# Drive.net
KiCad netlist of a schematic drawn in Altium Designer
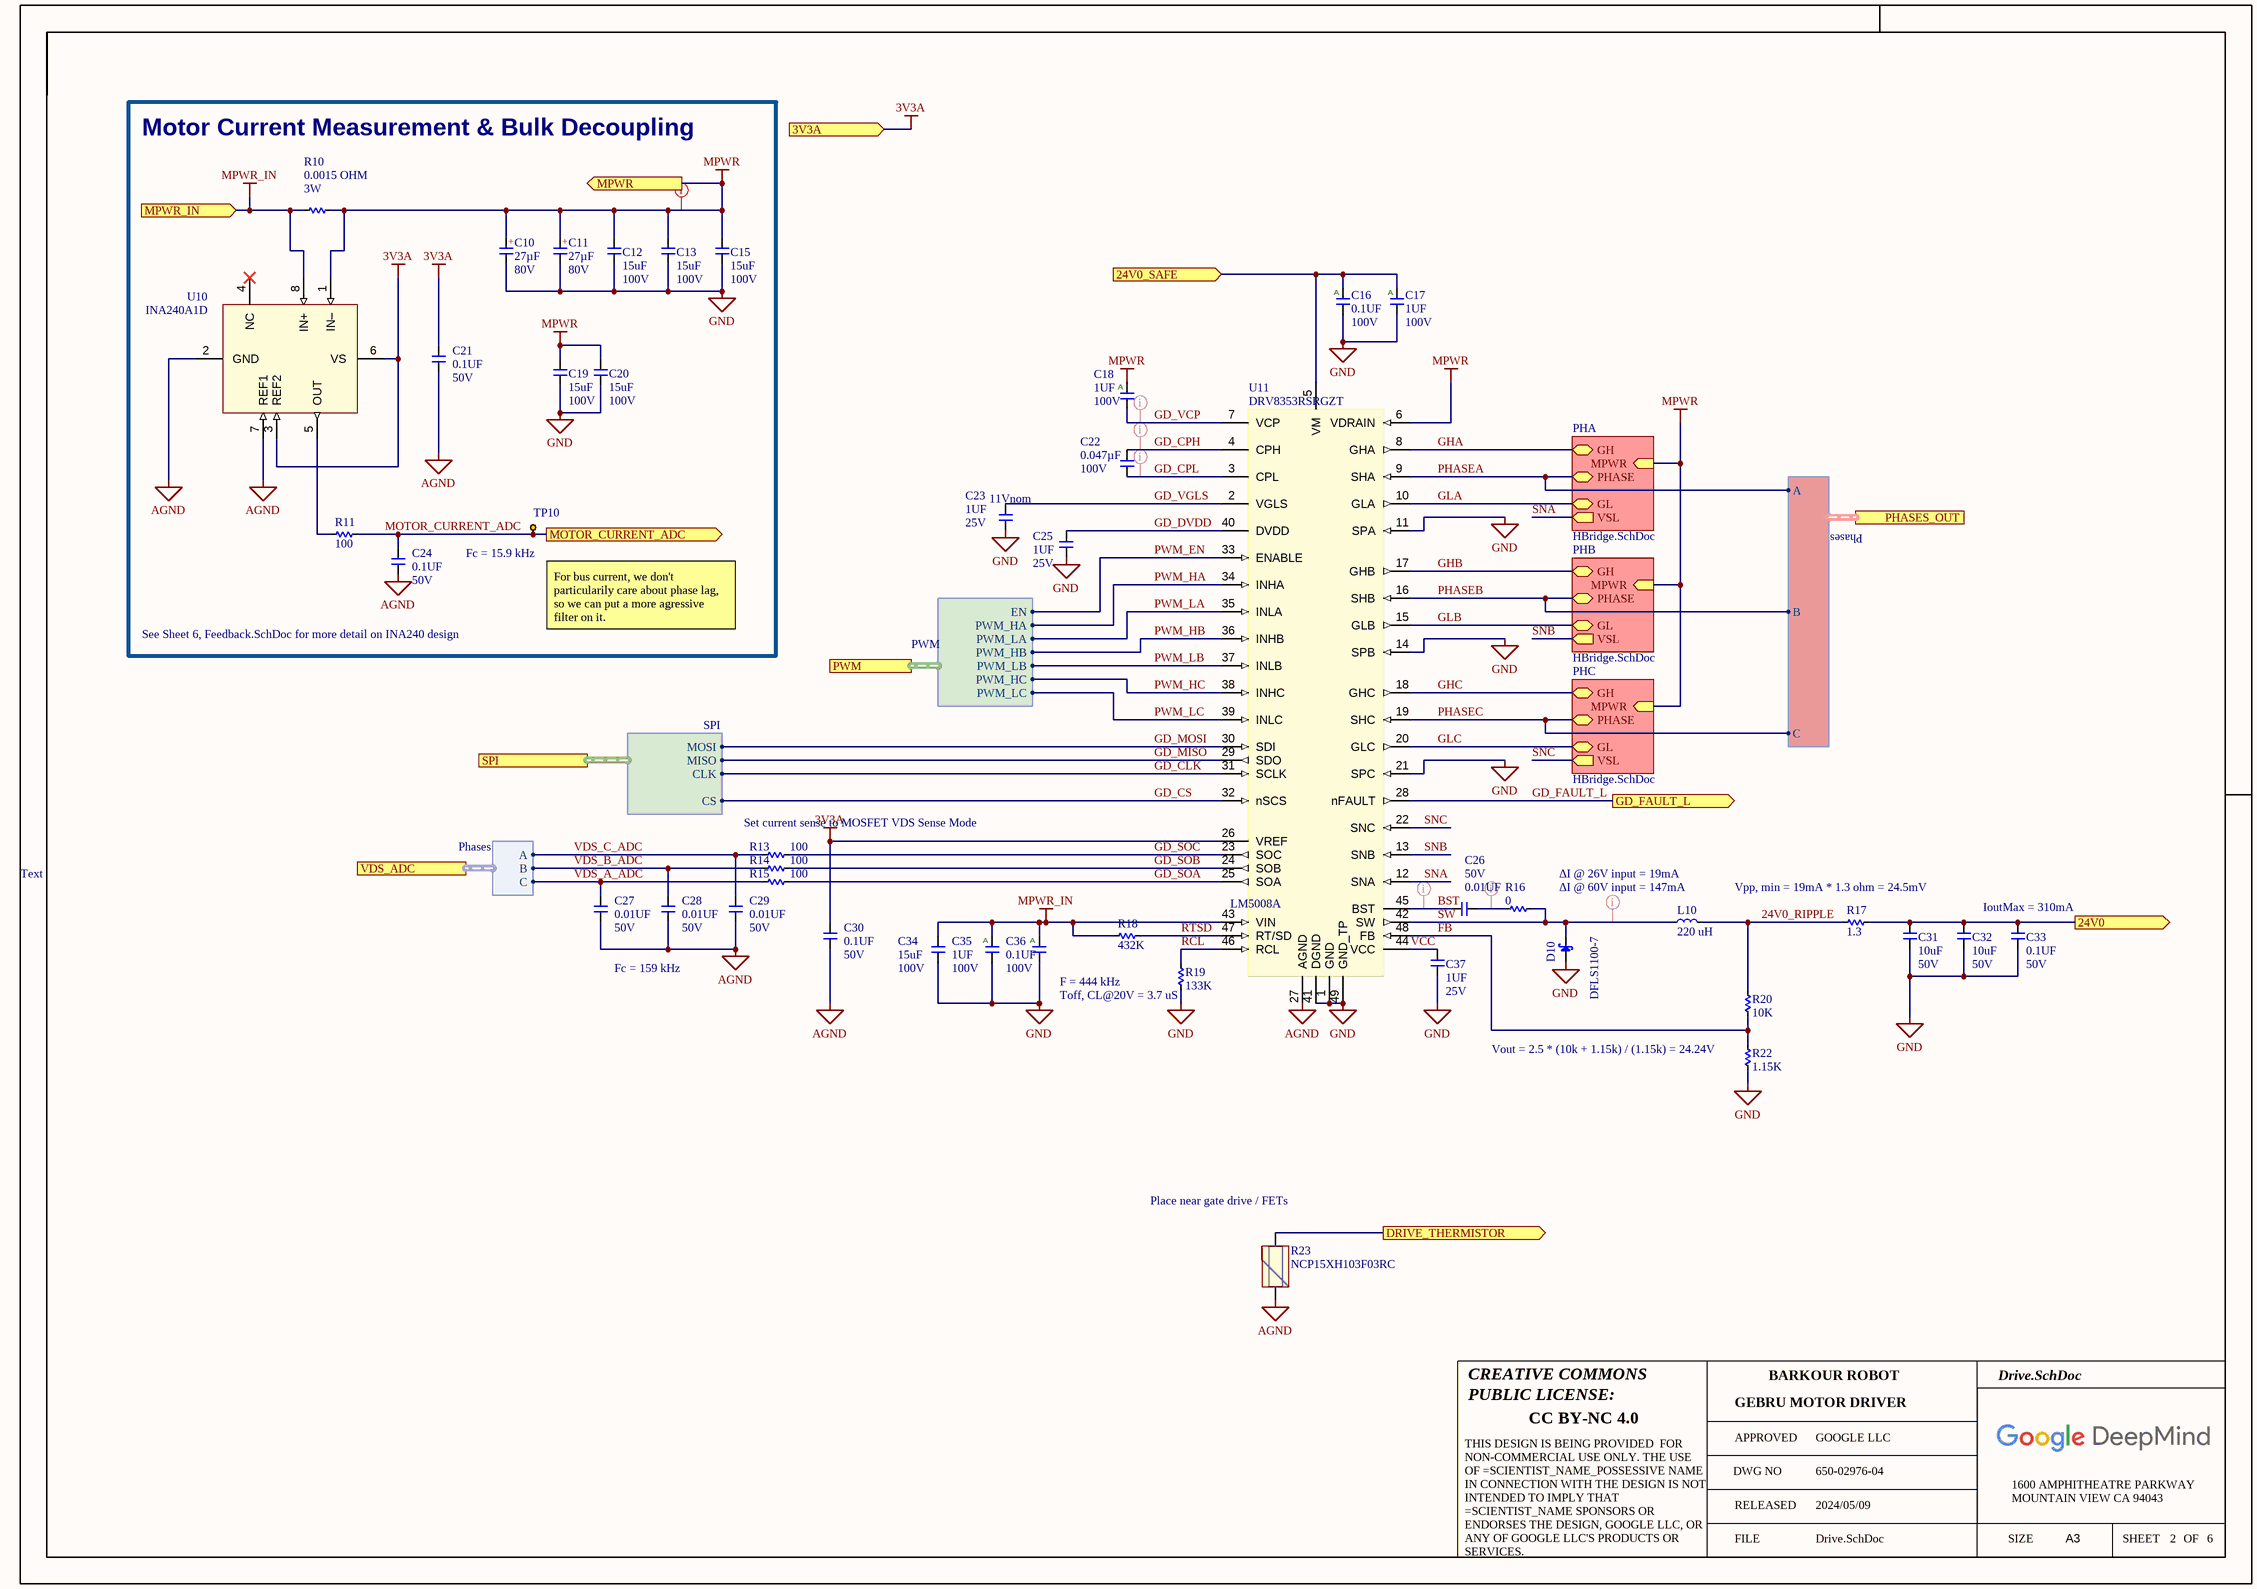
[diagram p0: Drive.SchDoc]

(export (version "E")
  (design (tool "Eeschema 10.0.6"))
  (components
    (comp (ref "C10")
      (value "27µF")
      (footprint "WURTH_WCAP-PTHR_10x12.5x5")
      (description "WCAP-PTHR ALUMINUM POLYMER CAP")
      (fields
        (field (name "MANUFACTURER") "Wurth Electronics")
        (field (name "MANUFACTURER PART NUMBER") "870056175004")
        (field (name "VOLTAGE RATING") "80V")
      )
      (libsource (lib "Components") (part "CAP-POL"))
    )
    (comp (ref "C11")
      (value "27µF")
      (footprint "WURTH_WCAP-PTHR_10x12.5x5")
      (description "WCAP-PTHR ALUMINUM POLYMER CAP")
      (fields
        (field (name "MANUFACTURER") "Wurth Electronics")
        (field (name "MANUFACTURER PART NUMBER") "870056175004")
        (field (name "VOLTAGE RATING") "80V")
      )
      (libsource (lib "Components") (part "CAP-POL"))
    )
    (comp (ref "C12")
      (value "15uF")
      (footprint "C2220")
      (description "CAP, CER, X7S, 15uF, 100V, 20%, 2220, 2.8mm T")
      (fields (field (name "MFG") "TDK") (field (name "VOLTAGE") "100V") (field (name "TOLERANCE") "20%"))
      (libsource (lib "AltiumReleaseLibDB") (part "__Template_Cap"))
    )
    (comp (ref "C13")
      (value "15uF")
      (footprint "C2220")
      (description "CAP, CER, X7S, 15uF, 100V, 20%, 2220, 2.8mm T")
      (fields (field (name "MFG") "TDK") (field (name "VOLTAGE") "100V") (field (name "TOLERANCE") "20%"))
      (libsource (lib "AltiumReleaseLibDB") (part "__Template_Cap"))
    )
    (comp (ref "C15")
      (value "15uF")
      (footprint "C2220")
      (description "CAP, CER, X7S, 15uF, 100V, 20%, 2220, 2.8mm T")
      (fields (field (name "MFG") "TDK") (field (name "VOLTAGE") "100V") (field (name "TOLERANCE") "20%"))
      (libsource (lib "AltiumReleaseLibDB") (part "__Template_Cap"))
    )
    (comp (ref "C16")
      (value "0.1UF")
      (footprint "C0603")
      (description "CAP, CER, X7S, 0.1uF, 100V, 10%, 0603, AUTOGRADE")
      (fields (field (name "MFG") "TDK") (field (name "VOLTAGE") "100V") (field (name "TOLERANCE") "10%"))
      (libsource (lib "AltiumReleaseLibDB") (part "__Template_Cap_Auto"))
    )
    (comp (ref "C17")
      (value "1UF")
      (footprint "C0805")
      (description "CAP, CER, X7S, 1uF, 20%, 100V, 0805")
      (fields (field (name "MFG") "TDK") (field (name "VOLTAGE") "100V") (field (name "TOLERANCE") "20%"))
      (libsource (lib "AltiumReleaseLibDB") (part "__Template_Cap_Auto"))
    )
    (comp (ref "C18")
      (value "1UF")
      (footprint "C0805")
      (description "CAP, CER, X7S, 1uF, 20%, 100V, 0805")
      (fields (field (name "MFG") "TDK") (field (name "VOLTAGE") "100V") (field (name "TOLERANCE") "20%"))
      (libsource (lib "AltiumReleaseLibDB") (part "__Template_Cap_Auto"))
    )
    (comp (ref "C19")
      (value "15uF")
      (footprint "C2220")
      (description "CAP, CER, X7S, 15uF, 100V, 20%, 2220, 2.8mm T")
      (fields (field (name "MFG") "TDK") (field (name "VOLTAGE") "100V") (field (name "TOLERANCE") "20%"))
      (libsource (lib "AltiumReleaseLibDB") (part "__Template_Cap"))
    )
    (comp (ref "C20")
      (value "15uF")
      (footprint "C2220")
      (description "CAP, CER, X7S, 15uF, 100V, 20%, 2220, 2.8mm T")
      (fields (field (name "MFG") "TDK") (field (name "VOLTAGE") "100V") (field (name "TOLERANCE") "20%"))
      (libsource (lib "AltiumReleaseLibDB") (part "__Template_Cap"))
    )
    (comp (ref "C21")
      (value "0.1UF")
      (footprint "C0402")
      (description "CAP, CER, X5R, 0.1uF, 10%, 50V, 0402, 0.55mm")
      (fields (field (name "MFG") "YAGEO") (field (name "VOLTAGE") "50V") (field (name "TOLERANCE") "10%"))
      (libsource (lib "AltiumReleaseLibDB") (part "__Template_Cap"))
    )
    (comp (ref "C22")
      (value "0.047µF")
      (footprint "C0603Y")
      (description "CAP, CER, X7R, 0.047uF, 100V, 10%, 0603, AUTOGRADE")
      (fields
        (field (name "MFG") "Samsung Electro-Mechanics")
        (field (name "VOLTAGE") "100V")
        (field (name "TOLERANCE") "10%")
      )
      (libsource (lib "AltiumReleaseLibDB") (part "__Template_Cap"))
    )
    (comp (ref "C23")
      (value "1UF")
      (footprint "C0402")
      (description "CAP, CER, X5R, 1uF, 10%, 25V, 0402")
      (fields (field (name "MFG") "TDK") (field (name "VOLTAGE") "25V") (field (name "TOLERANCE") "10%"))
      (libsource (lib "AltiumReleaseLibDB") (part "__Template_Cap"))
    )
    (comp (ref "C24")
      (value "0.1UF")
      (footprint "C0402")
      (description "CAP, CER, X5R, 0.1uF, 10%, 50V, 0402, 0.55mm")
      (fields (field (name "MFG") "YAGEO") (field (name "VOLTAGE") "50V") (field (name "TOLERANCE") "10%"))
      (libsource (lib "AltiumReleaseLibDB") (part "__Template_Cap"))
    )
    (comp (ref "C25")
      (value "1UF")
      (footprint "C0402")
      (description "CAP, CER, X5R, 1uF, 10%, 25V, 0402")
      (fields (field (name "MFG") "TDK") (field (name "VOLTAGE") "25V") (field (name "TOLERANCE") "10%"))
      (libsource (lib "AltiumReleaseLibDB") (part "__Template_Cap"))
    )
    (comp (ref "C26")
      (value "0.01UF")
      (footprint "C0402")
      (description "CAP, CER, X7R, 0.01uF, 50V, 20%, 0402, 0.56mm T")
      (fields (field (name "MFG") "KEMET") (field (name "VOLTAGE") "50V") (field (name "TOLERANCE") "20%"))
      (libsource (lib "AltiumReleaseLibDB") (part "__Template_Cap"))
    )
    (comp (ref "C27")
      (value "0.01UF")
      (footprint "C0402")
      (description "CAP, CER, X7R, 0.01uF, 50V, 20%, 0402, 0.56mm T")
      (fields (field (name "MFG") "KEMET") (field (name "VOLTAGE") "50V") (field (name "TOLERANCE") "20%"))
      (libsource (lib "AltiumReleaseLibDB") (part "__Template_Cap"))
    )
    (comp (ref "C28")
      (value "0.01UF")
      (footprint "C0402")
      (description "CAP, CER, X7R, 0.01uF, 50V, 20%, 0402, 0.56mm T")
      (fields (field (name "MFG") "KEMET") (field (name "VOLTAGE") "50V") (field (name "TOLERANCE") "20%"))
      (libsource (lib "AltiumReleaseLibDB") (part "__Template_Cap"))
    )
    (comp (ref "C29")
      (value "0.01UF")
      (footprint "C0402")
      (description "CAP, CER, X7R, 0.01uF, 50V, 20%, 0402, 0.56mm T")
      (fields (field (name "MFG") "KEMET") (field (name "VOLTAGE") "50V") (field (name "TOLERANCE") "20%"))
      (libsource (lib "AltiumReleaseLibDB") (part "__Template_Cap"))
    )
    (comp (ref "C30")
      (value "0.1UF")
      (footprint "C0402")
      (description "CAP, CER, X5R, 0.1uF, 10%, 50V, 0402, 0.55mm")
      (fields (field (name "MFG") "YAGEO") (field (name "VOLTAGE") "50V") (field (name "TOLERANCE") "10%"))
      (libsource (lib "AltiumReleaseLibDB") (part "__Template_Cap"))
    )
    (comp (ref "C31")
      (value "10uF")
      (footprint "C1210_H2.7mm")
      (description "CAP, CER, X5R, 10uF, 50V, 20%, 1210")
      (fields
        (field (name "MFG") "TAIYO YUDEN")
        (field (name "VOLTAGE") "50V")
        (field (name "TOLERANCE") "20%")
      )
      (libsource (lib "AltiumReleaseLibDB") (part "__Template_Cap"))
    )
    (comp (ref "C32")
      (value "10uF")
      (footprint "C1210_H2.7mm")
      (description "CAP, CER, X5R, 10uF, 50V, 20%, 1210")
      (fields
        (field (name "MFG") "TAIYO YUDEN")
        (field (name "VOLTAGE") "50V")
        (field (name "TOLERANCE") "20%")
      )
      (libsource (lib "AltiumReleaseLibDB") (part "__Template_Cap"))
    )
    (comp (ref "C33")
      (value "0.1UF")
      (footprint "C0402")
      (description "CAP, CER, X5R, 0.1uF, 10%, 50V, 0402, 0.55mm")
      (fields (field (name "MFG") "YAGEO") (field (name "VOLTAGE") "50V") (field (name "TOLERANCE") "10%"))
      (libsource (lib "AltiumReleaseLibDB") (part "__Template_Cap"))
    )
    (comp (ref "C34")
      (value "15uF")
      (footprint "C2220")
      (description "CAP, CER, X7S, 15uF, 100V, 20%, 2220, 2.8mm T")
      (fields (field (name "MFG") "TDK") (field (name "VOLTAGE") "100V") (field (name "TOLERANCE") "20%"))
      (libsource (lib "AltiumReleaseLibDB") (part "__Template_Cap"))
    )
    (comp (ref "C35")
      (value "1UF")
      (footprint "C0805")
      (description "CAP, CER, X7S, 1uF, 20%, 100V, 0805")
      (fields (field (name "MFG") "TDK") (field (name "VOLTAGE") "100V") (field (name "TOLERANCE") "20%"))
      (libsource (lib "AltiumReleaseLibDB") (part "__Template_Cap_Auto"))
    )
    (comp (ref "C36")
      (value "0.1UF")
      (footprint "C0603")
      (description "CAP, CER, X7S, 0.1uF, 100V, 10%, 0603, AUTOGRADE")
      (fields (field (name "MFG") "TDK") (field (name "VOLTAGE") "100V") (field (name "TOLERANCE") "10%"))
      (libsource (lib "AltiumReleaseLibDB") (part "__Template_Cap_Auto"))
    )
    (comp (ref "C37")
      (value "1UF")
      (footprint "C0402")
      (description "CAP, CER, X5R, 1uF, 10%, 25V, 0402")
      (fields (field (name "MFG") "TDK") (field (name "VOLTAGE") "25V") (field (name "TOLERANCE") "10%"))
      (libsource (lib "AltiumReleaseLibDB") (part "__Template_Cap"))
    )
    (comp (ref "D10")
      (value "DFLS1100-7")
      (footprint "POWERDI123_DFLS1100-7")
      (description "DIODE, SCHOTTKY, 100V, 1A, POWERDI123")
      (fields
        (field (name "MFG") "Diodes Incorporated")
        (field (name "Comment") "__Template_Diode_Schottky_A/K")
      )
      (libsource (lib "AltiumReleaseLibDB") (part "__Template_Diode_Schottky_A/K"))
    )
    (comp (ref "L10")
      (value "220 uH")
      (footprint "IND_MSS7348")
      (description "IND, WIREWOUND, SHIELDED, 220uH, 0.74A, 20%, DCR 0.624, SMD, AUTOGRADE")
      (fields (field (name "MFG") "Coilcraft") (field (name "TOLERANCE") "20%"))
      (libsource (lib "AltiumReleaseLibDB") (part "__Template_Inductor"))
    )
    (comp (ref "R10")
      (value "0.0015 OHM")
      (footprint "R2512_H0.8MM")
      (description "RES, 0.0015, 1%, 3W, 2512")
      (fields
        (field (name "MFG") "TE Connectivity Passive Product")
        (field (name "POWER") "3W")
        (field (name "TOLERANCE") "1%")
      )
      (libsource (lib "AltiumReleaseLibDB") (part "__Template_Resistor"))
    )
    (comp (ref "R11")
      (value "100")
      (footprint "R0402")
      (description "RES, 100, 1%, 1/10W, 0402, AUTO GRADE")
      (fields (field (name "MFG") "PANASONIC") (field (name "POWER") "1/10W"))
      (libsource (lib "AltiumReleaseLibDB") (part "__Template_Resistor"))
    )
    (comp (ref "R13")
      (value "100")
      (footprint "R0402")
      (description "RES, 100, 1%, 1/10W, 0402, AUTO GRADE")
      (fields (field (name "MFG") "PANASONIC") (field (name "POWER") "1/10W"))
      (libsource (lib "AltiumReleaseLibDB") (part "__Template_Resistor"))
    )
    (comp (ref "R14")
      (value "100")
      (footprint "R0402")
      (description "RES, 100, 1%, 1/10W, 0402, AUTO GRADE")
      (fields (field (name "MFG") "PANASONIC") (field (name "POWER") "1/10W"))
      (libsource (lib "AltiumReleaseLibDB") (part "__Template_Resistor"))
    )
    (comp (ref "R15")
      (value "100")
      (footprint "R0402")
      (description "RES, 100, 1%, 1/10W, 0402, AUTO GRADE")
      (fields (field (name "MFG") "PANASONIC") (field (name "POWER") "1/10W"))
      (libsource (lib "AltiumReleaseLibDB") (part "__Template_Resistor"))
    )
    (comp (ref "R16")
      (value "0")
      (footprint "R0402")
      (description "RES, 0, JUMPER, 1/16W, 0402")
      (fields (field (name "MFG") "YAGEO") (field (name "POWER") "1/16W"))
      (libsource (lib "AltiumReleaseLibDB") (part "__Template_Resistor"))
    )
    (comp (ref "R17")
      (value "1.3")
      (footprint "R0805")
      (description "RES, 1.3, 1%, 1/2W, AUTOGRADE, 0805")
      (fields (field (name "MFG") "Panasonic Electronic Components") (field (name "POWER") "1/2W"))
      (libsource (lib "AltiumReleaseLibDB") (part "__Template_Resistor"))
    )
    (comp (ref "R18")
      (value "432K")
      (footprint "R0402")
      (description "RES, 432K, 1%, 1/16W, 0402")
      (fields (field (name "MFG") "VISHAY") (field (name "POWER") "1/16W"))
      (libsource (lib "AltiumReleaseLibDB") (part "__Template_Resistor"))
    )
    (comp (ref "R19")
      (value "133K")
      (footprint "R0402")
      (description "RES, 133K, 1%, 1/16W, 0402, AUTOGRADE")
      (fields (field (name "MFG") "VISHAY") (field (name "POWER") "1/16W"))
      (libsource (lib "AltiumReleaseLibDB") (part "__Template_Resistor"))
    )
    (comp (ref "R20")
      (value "10K")
      (footprint "R0402")
      (description "RES, 10K, 1%, 1/10W, 0402, AUTOGRADE")
      (fields (field (name "MFG") "PANASONIC") (field (name "POWER") "1/10W"))
      (libsource (lib "AltiumReleaseLibDB") (part "__Template_Resistor"))
    )
    (comp (ref "R22")
      (value "1.15K")
      (footprint "R0402")
      (description "RES, 1.15K, 1%, 1/16W, 0402")
      (fields (field (name "MFG") "VISHAY") (field (name "POWER") "1/16W"))
      (libsource (lib "AltiumReleaseLibDB") (part "__Template_Resistor"))
    )
    (comp (ref "R23")
      (value "__Template_Thermistor")
      (footprint "R0402_H0.55MM")
      (description "SENSOR, THERMISTOR, NTC, 10K, 1%, 3380K, 100mW, 0402")
      (fields (field (name "MFG") "Murata Electronics") (field (name "MFG P/N") "NCP15XH103F03RC"))
      (libsource (lib "AltiumReleaseLibDB") (part "__Template_Thermistor"))
    )
    (comp (ref "TP10")
      (value "TEST_KEYSTONE5015")
      (footprint "TP_KEYSTONE_5015")
      (description "PC TEST POINT MINIATURE SMT")
      (fields
        (field (name "MANUFACTURER") "Keystone Electronics")
        (field (name "MANUFACTURER PART NUMBER") "5015")
      )
      (libsource (lib "miscellaneous") (part "TEST_KEYSTONE5015"))
    )
    (comp (ref "U10")
      (value "INA240A1D")
      (footprint "TI SOIC-8 D0008A")
      (fields (field (name "MANUFACTURER") "Texas Instruments"))
      (libsource (lib "MiscSch1") (part "INA240A1"))
    )
    (comp (ref "U11")
      (value "MOTOR_DRIVE_DRV8353RSRGZT")
      (footprint "VQFN50P700X700X100-48-TP_TP-CUST_NO_VIAS")
      (description "IC, MOTOR DRIVER, DRV8353, MULTIPHASE, BLDC, HALF BRIDGE, POWER MOSFET, 6V TO 95V VIN, VQFN-48")
      (fields (field (name "MFG") "Texas Instruments") (field (name "MFG P/N") "DRV8353RSRGZT"))
      (libsource (lib "AltiumReleaseLibDB") (part "MOTOR_DRIVE_DRV8353RSRGZT"))
    )
  )
  (nets
    (net (code "4") (name "/24V0") (class "Default")
      (node (ref "C31") (pin "1") (pintype "passive"))
      (node (ref "C32") (pin "1") (pintype "passive"))
      (node (ref "C33") (pin "1") (pintype "passive"))
      (node (ref "R17") (pin "2") (pintype "passive"))
    )
    (net (code "5") (name "/24V0_RIPPLE") (class "Default")
      (node (ref "L10") (pin "2") (pintype "passive"))
      (node (ref "R17") (pin "1") (pintype "passive"))
      (node (ref "R20") (pin "2") (pintype "passive"))
    )
    (net (code "6") (name "/24V0_SAFE") (class "Default")
      (node (ref "C16") (pin "1") (pintype "passive"))
      (node (ref "C17") (pin "1") (pintype "passive"))
      (node (ref "U11") (pin "5") (pinfunction "VM_5") (pintype "power_in"))
    )
    (net (code "7") (name "/BST") (class "Default")
      (node (ref "C26") (pin "1") (pintype "passive"))
      (node (ref "U11") (pin "45") (pinfunction "BST_45") (pintype "power_in"))
    )
    (net (code "8") (name "/DRIVE_THERMISTOR") (class "Default")
      (node (ref "R23") (pin "1") (pintype "passive"))
    )
    (net (code "9") (name "/FB") (class "Default")
      (node (ref "R20") (pin "1") (pintype "passive"))
      (node (ref "R22") (pin "2") (pintype "passive"))
      (node (ref "U11") (pin "48") (pinfunction "FB_48") (pintype "input"))
    )
    (net (code "10") (name "/GD_CLK") (class "Default")
      (node (ref "U11") (pin "31") (pinfunction "SCLK_31") (pintype "input"))
    )
    (net (code "11") (name "/GD_CPH") (class "Default")
      (node (ref "C22") (pin "1") (pintype "passive"))
      (node (ref "U11") (pin "4") (pinfunction "CPH_4") (pintype "power_in"))
    )
    (net (code "12") (name "/GD_CPL") (class "Default")
      (node (ref "C22") (pin "2") (pintype "passive"))
      (node (ref "U11") (pin "3") (pinfunction "CPL_3") (pintype "power_in"))
    )
    (net (code "13") (name "/GD_CS") (class "Default")
      (node (ref "U11") (pin "32") (pinfunction "nSCS_32") (pintype "input"))
    )
    (net (code "14") (name "/GD_DVDD") (class "Default")
      (node (ref "C25") (pin "1") (pintype "passive"))
      (node (ref "U11") (pin "40") (pinfunction "DVDD_40") (pintype "power_in"))
    )
    (net (code "15") (name "/GD_FAULT_L") (class "Default")
      (node (ref "U11") (pin "28") (pinfunction "nFAULT_28") (pintype "output"))
    )
    (net (code "16") (name "/GD_MISO") (class "Default")
      (node (ref "U11") (pin "29") (pinfunction "SDO_29") (pintype "output"))
    )
    (net (code "17") (name "/GD_MOSI") (class "Default")
      (node (ref "U11") (pin "30") (pinfunction "SDI_30") (pintype "input"))
    )
    (net (code "18") (name "/GD_SOA") (class "Default")
      (node (ref "R15") (pin "2") (pintype "passive"))
      (node (ref "U11") (pin "25") (pinfunction "SOA_25") (pintype "output"))
    )
    (net (code "19") (name "/GD_SOB") (class "Default")
      (node (ref "R14") (pin "2") (pintype "passive"))
      (node (ref "U11") (pin "24") (pinfunction "SOB_24") (pintype "output"))
    )
    (net (code "20") (name "/GD_SOC") (class "Default")
      (node (ref "R13") (pin "2") (pintype "passive"))
      (node (ref "U11") (pin "23") (pinfunction "SOC_23") (pintype "output"))
    )
    (net (code "21") (name "/GD_VCP") (class "Default")
      (node (ref "C18") (pin "2") (pintype "passive"))
      (node (ref "U11") (pin "7") (pinfunction "VCP_7") (pintype "power_in"))
    )
    (net (code "22") (name "/GD_VGLS") (class "Default")
      (node (ref "C23") (pin "1") (pintype "passive"))
      (node (ref "U11") (pin "2") (pinfunction "VGLS_2") (pintype "power_in"))
    )
    (net (code "23") (name "/GHA") (class "Default")
      (node (ref "U11") (pin "8") (pinfunction "GHA_8") (pintype "output"))
    )
    (net (code "24") (name "/GHB") (class "Default")
      (node (ref "U11") (pin "17") (pinfunction "GHB_17") (pintype "output"))
    )
    (net (code "25") (name "/GHC") (class "Default")
      (node (ref "U11") (pin "18") (pinfunction "GHC_18") (pintype "output"))
    )
    (net (code "26") (name "/GLA") (class "Default")
      (node (ref "U11") (pin "10") (pinfunction "GLA_10") (pintype "output"))
    )
    (net (code "27") (name "/GLB") (class "Default")
      (node (ref "U11") (pin "15") (pinfunction "GLB_15") (pintype "output"))
    )
    (net (code "28") (name "/GLC") (class "Default")
      (node (ref "U11") (pin "20") (pinfunction "GLC_20") (pintype "output"))
    )
    (net (code "29") (name "/MOTOR_CURRENT_ADC") (class "Default")
      (node (ref "C24") (pin "1") (pintype "passive"))
      (node (ref "R11") (pin "2") (pintype "passive"))
      (node (ref "TP10") (pin "1") (pintype "passive"))
    )
    (net (code "30") (name "/PHASEA") (class "Default")
      (node (ref "U11") (pin "9") (pinfunction "SHA_9") (pintype "input"))
    )
    (net (code "31") (name "/PHASEB") (class "Default")
      (node (ref "U11") (pin "16") (pinfunction "SHB_16") (pintype "input"))
    )
    (net (code "32") (name "/PHASEC") (class "Default")
      (node (ref "U11") (pin "19") (pinfunction "SHC_19") (pintype "input"))
    )
    (net (code "33") (name "/PWM_EN") (class "Default")
      (node (ref "U11") (pin "33") (pinfunction "ENABLE_33") (pintype "input"))
    )
    (net (code "34") (name "/PWM_HA") (class "Default")
      (node (ref "U11") (pin "34") (pinfunction "INHA_34") (pintype "input"))
    )
    (net (code "35") (name "/PWM_HB") (class "Default")
      (node (ref "U11") (pin "36") (pinfunction "INHB_36") (pintype "input"))
    )
    (net (code "36") (name "/PWM_HC") (class "Default")
      (node (ref "U11") (pin "38") (pinfunction "INHC_38") (pintype "input"))
    )
    (net (code "37") (name "/PWM_LA") (class "Default")
      (node (ref "U11") (pin "35") (pinfunction "INLA_35") (pintype "input"))
    )
    (net (code "38") (name "/PWM_LB") (class "Default")
      (node (ref "U11") (pin "37") (pinfunction "INLB_37") (pintype "input"))
    )
    (net (code "39") (name "/PWM_LC") (class "Default")
      (node (ref "U11") (pin "39") (pinfunction "INLC_39") (pintype "input"))
    )
    (net (code "40") (name "/RCL") (class "Default")
      (node (ref "R19") (pin "2") (pintype "passive"))
      (node (ref "U11") (pin "46") (pinfunction "RCL_46") (pintype "input"))
    )
    (net (code "41") (name "/RTSD") (class "Default")
      (node (ref "R18") (pin "2") (pintype "passive"))
      (node (ref "U11") (pin "47") (pinfunction "RT/SD_47") (pintype "input"))
    )
    (net (code "42") (name "/SNA") (class "Default")
      (node (ref "U11") (pin "12") (pinfunction "SNA_12") (pintype "input"))
    )
    (net (code "43") (name "/SNB") (class "Default")
      (node (ref "U11") (pin "13") (pinfunction "SNB_13") (pintype "input"))
    )
    (net (code "44") (name "/SNC") (class "Default")
      (node (ref "U11") (pin "22") (pinfunction "SNC_22") (pintype "input"))
    )
    (net (code "45") (name "/SW") (class "Default")
      (node (ref "D10") (pin "K") (pintype "passive"))
      (node (ref "L10") (pin "1") (pintype "passive"))
      (node (ref "R16") (pin "2") (pintype "passive"))
      (node (ref "U11") (pin "42") (pinfunction "SW_42") (pintype "output"))
    )
    (net (code "46") (name "/VCC") (class "Default")
      (node (ref "C37") (pin "1") (pintype "passive"))
      (node (ref "U11") (pin "44") (pinfunction "VCC_44") (pintype "power_in"))
    )
    (net (code "47") (name "/VDS_A_ADC") (class "Default")
      (node (ref "C27") (pin "1") (pintype "passive"))
      (node (ref "R15") (pin "1") (pintype "passive"))
    )
    (net (code "48") (name "/VDS_B_ADC") (class "Default")
      (node (ref "C28") (pin "1") (pintype "passive"))
      (node (ref "R14") (pin "1") (pintype "passive"))
    )
    (net (code "49") (name "/VDS_C_ADC") (class "Default")
      (node (ref "C29") (pin "1") (pintype "passive"))
      (node (ref "R13") (pin "1") (pintype "passive"))
    )
    (net (code "53") (name "3V3A") (class "Default")
      (node (ref "C21") (pin "1") (pintype "passive"))
      (node (ref "C30") (pin "1") (pintype "passive"))
      (node (ref "U10") (pin "3") (pinfunction "REF2_3") (pintype "input"))
      (node (ref "U10") (pin "6") (pinfunction "VS_6") (pintype "power_in"))
      (node (ref "U11") (pin "26") (pinfunction "VREF_26") (pintype "power_in"))
    )
    (net (code "54") (name "AGND") (class "Default")
      (node (ref "C21") (pin "2") (pintype "passive"))
      (node (ref "C24") (pin "2") (pintype "passive"))
      (node (ref "C27") (pin "2") (pintype "passive"))
      (node (ref "C28") (pin "2") (pintype "passive"))
      (node (ref "C29") (pin "2") (pintype "passive"))
      (node (ref "C30") (pin "2") (pintype "passive"))
      (node (ref "R23") (pin "2") (pintype "passive"))
      (node (ref "U10") (pin "2") (pinfunction "GND_2") (pintype "power_in"))
      (node (ref "U10") (pin "7") (pinfunction "REF1_7") (pintype "input"))
      (node (ref "U11") (pin "27") (pinfunction "AGND_27") (pintype "power_in"))
    )
    (net (code "55") (name "GND") (class "Default")
      (node (ref "C10") (pin "2") (pintype "passive"))
      (node (ref "C11") (pin "2") (pintype "passive"))
      (node (ref "C12") (pin "2") (pintype "passive"))
      (node (ref "C13") (pin "2") (pintype "passive"))
      (node (ref "C15") (pin "2") (pintype "passive"))
      (node (ref "C16") (pin "2") (pintype "passive"))
      (node (ref "C17") (pin "2") (pintype "passive"))
      (node (ref "C19") (pin "2") (pintype "passive"))
      (node (ref "C20") (pin "2") (pintype "passive"))
      (node (ref "C23") (pin "2") (pintype "passive"))
      (node (ref "C25") (pin "2") (pintype "passive"))
      (node (ref "C31") (pin "2") (pintype "passive"))
      (node (ref "C32") (pin "2") (pintype "passive"))
      (node (ref "C33") (pin "2") (pintype "passive"))
      (node (ref "C34") (pin "2") (pintype "passive"))
      (node (ref "C35") (pin "2") (pintype "passive"))
      (node (ref "C36") (pin "2") (pintype "passive"))
      (node (ref "C37") (pin "2") (pintype "passive"))
      (node (ref "D10") (pin "A") (pintype "passive"))
      (node (ref "R19") (pin "1") (pintype "passive"))
      (node (ref "R22") (pin "1") (pintype "passive"))
      (node (ref "U11") (pin "1") (pinfunction "GND_1") (pintype "power_in"))
      (node (ref "U11") (pin "11") (pinfunction "SPA_11") (pintype "input"))
      (node (ref "U11") (pin "14") (pinfunction "SPB_14") (pintype "input"))
      (node (ref "U11") (pin "21") (pinfunction "SPC_21") (pintype "input"))
      (node (ref "U11") (pin "41") (pinfunction "DGND_41") (pintype "power_in"))
      (node (ref "U11") (pin "49") (pinfunction "GND_TP_49") (pintype "power_in"))
    )
    (net (code "56") (name "MPWR") (class "Default")
      (node (ref "C10") (pin "1") (pintype "passive"))
      (node (ref "C11") (pin "1") (pintype "passive"))
      (node (ref "C12") (pin "1") (pintype "passive"))
      (node (ref "C13") (pin "1") (pintype "passive"))
      (node (ref "C15") (pin "1") (pintype "passive"))
      (node (ref "C18") (pin "1") (pintype "passive"))
      (node (ref "C19") (pin "1") (pintype "passive"))
      (node (ref "C20") (pin "1") (pintype "passive"))
      (node (ref "R10") (pin "2") (pintype "passive"))
      (node (ref "U10") (pin "1") (pinfunction "IN–_1") (pintype "input"))
      (node (ref "U11") (pin "6") (pinfunction "VDRAIN_6") (pintype "input"))
    )
    (net (code "57") (name "MPWR_IN") (class "Default")
      (node (ref "C34") (pin "1") (pintype "passive"))
      (node (ref "C35") (pin "1") (pintype "passive"))
      (node (ref "C36") (pin "1") (pintype "passive"))
      (node (ref "R10") (pin "1") (pintype "passive"))
      (node (ref "R18") (pin "1") (pintype "passive"))
      (node (ref "U10") (pin "8") (pinfunction "IN+_8") (pintype "input"))
      (node (ref "U11") (pin "43") (pinfunction "VIN_43") (pintype "input"))
    )
    (net (code "58") (name "Net-(C26-Pad2)") (class "Default")
      (node (ref "C26") (pin "2") (pintype "passive"))
      (node (ref "R16") (pin "1") (pintype "passive"))
    )
    (net (code "59") (name "Net-(U10-OUT)") (class "Default")
      (node (ref "R11") (pin "1") (pintype "passive"))
      (node (ref "U10") (pin "5") (pinfunction "OUT_5") (pintype "output"))
    )
    (net (code "60") (name "unconnected-(U10-NC-Pad4)") (class "Default")
      (node (ref "U10") (pin "4") (pinfunction "NC_4") (pintype "passive+no_connect"))
    )
  )
)
